# MS_20_Filter_Geetah.net
KiCad netlist of a schematic drawn in EAGLE
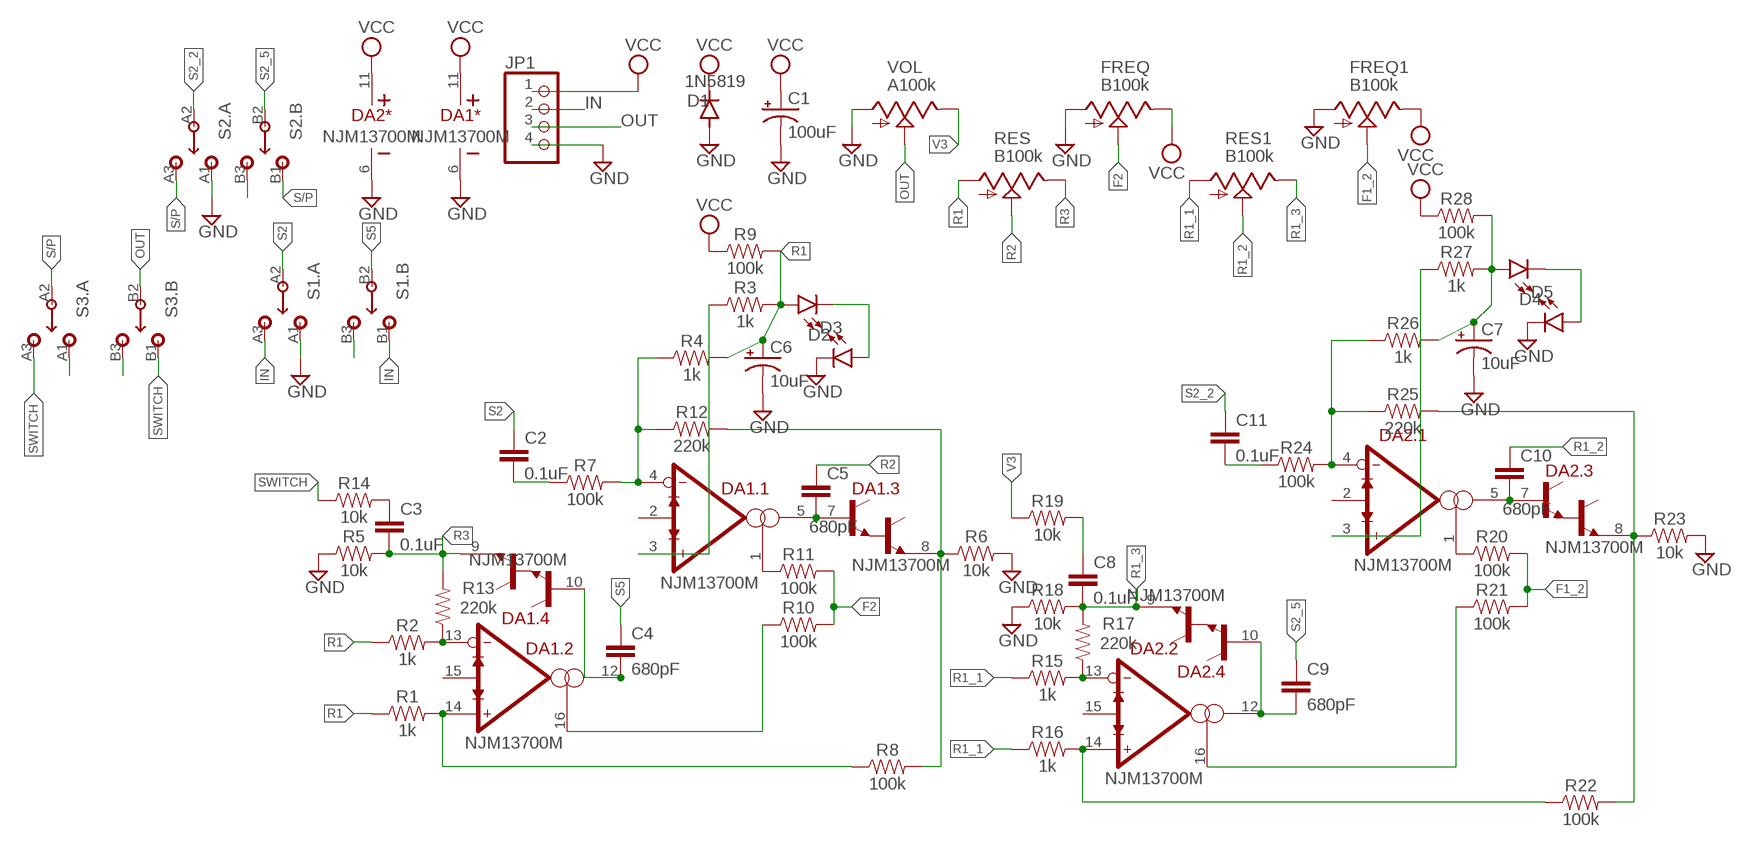
[diagram p0: schematic, sheet 1]

(export (version "E")
  (design (tool "Eeschema 10.0.6"))
  (components
    (comp (ref "C1")
      (value "100uF")
      (footprint "eagle-import:PAN_B_SMD+THRU")
      (libsource (lib "eagle-import") (part "CAP_SMD+THRUPAN_B"))
    )
    (comp (ref "C2")
      (value "0.1uF")
      (footprint "eagle-import:0603")
      (libsource (lib "eagle-import") (part "0.1UF-0603-25V-(+80/-20%)"))
    )
    (comp (ref "C3")
      (value "0.1uF")
      (footprint "eagle-import:0603")
      (libsource (lib "eagle-import") (part "0.1UF-0603-25V-(+80/-20%)"))
    )
    (comp (ref "C4")
      (value "680pF")
      (footprint "eagle-import:0603")
      (libsource (lib "eagle-import") (part "680PF-0603-50V-10%"))
    )
    (comp (ref "C5")
      (value "680pF")
      (footprint "eagle-import:0603")
      (libsource (lib "eagle-import") (part "680PF-0603-50V-10%"))
    )
    (comp (ref "C6")
      (value "10uF")
      (footprint "eagle-import:PAN_B_SMD+THRU")
      (libsource (lib "eagle-import") (part "CAP_SMD+THRUPAN_B"))
    )
    (comp (ref "C7")
      (value "10uF")
      (footprint "eagle-import:PAN_B_SMD+THRU")
      (libsource (lib "eagle-import") (part "CAP_SMD+THRUPAN_B"))
    )
    (comp (ref "C8")
      (value "0.1uF")
      (footprint "eagle-import:0603")
      (libsource (lib "eagle-import") (part "0.1UF-0603-25V-(+80/-20%)"))
    )
    (comp (ref "C9")
      (value "680pF")
      (footprint "eagle-import:0603")
      (libsource (lib "eagle-import") (part "680PF-0603-50V-10%"))
    )
    (comp (ref "C10")
      (value "680pF")
      (footprint "eagle-import:0603")
      (libsource (lib "eagle-import") (part "680PF-0603-50V-10%"))
    )
    (comp (ref "C11")
      (value "0.1uF")
      (footprint "eagle-import:0603")
      (libsource (lib "eagle-import") (part "0.1UF-0603-25V-(+80/-20%)"))
    )
    (comp (ref "D1")
      (value "1N5819")
      (footprint "eagle-import:SOD123")
      (libsource (lib "eagle-import") (part "DIODE-SOD123"))
    )
    (comp (ref "D2")
      (value "LED-FKIT-1206")
      (footprint "eagle-import:FKIT-LED-1206")
      (libsource (lib "eagle-import") (part "LED-FKIT-1206"))
    )
    (comp (ref "D3")
      (value "LED-FKIT-1206")
      (footprint "eagle-import:FKIT-LED-1206")
      (libsource (lib "eagle-import") (part "LED-FKIT-1206"))
    )
    (comp (ref "D4")
      (value "LED-FKIT-1206")
      (footprint "eagle-import:FKIT-LED-1206")
      (libsource (lib "eagle-import") (part "LED-FKIT-1206"))
    )
    (comp (ref "D5")
      (value "LED-FKIT-1206")
      (footprint "eagle-import:FKIT-LED-1206")
      (libsource (lib "eagle-import") (part "LED-FKIT-1206"))
    )
    (comp (ref "DA1")
      (value "NJM13700M")
      (footprint "eagle-import:SO-16")
      (libsource (lib "eagle-import") (part "NJM13700M"))
    )
    (comp (ref "DA2")
      (value "NJM13700M")
      (footprint "eagle-import:SO-16")
      (libsource (lib "eagle-import") (part "NJM13700M"))
    )
    (comp (ref "FREQ")
      (value "B100k")
      (footprint "eagle-import:9MM_SNAP-IN_POT")
      (libsource (lib "eagle-import") (part "9MM_SNAP-IN_POT_"))
    )
    (comp (ref "FREQ1")
      (value "B100k")
      (footprint "eagle-import:9MM_SNAP-IN_POT")
      (libsource (lib "eagle-import") (part "9MM_SNAP-IN_POT_"))
    )
    (comp (ref "JP1")
      (value "PINHD-1X4")
      (footprint "eagle-import:1X04")
      (libsource (lib "eagle-import") (part "PINHD-1X4"))
    )
    (comp (ref "R1")
      (value "1k")
      (footprint "eagle-import:0603")
      (libsource (lib "eagle-import") (part "1KOHM-0603-1/10W-1%"))
    )
    (comp (ref "R2")
      (value "1k")
      (footprint "eagle-import:0603")
      (libsource (lib "eagle-import") (part "1KOHM-0603-1/10W-1%"))
    )
    (comp (ref "R3")
      (value "1k")
      (footprint "eagle-import:0603")
      (libsource (lib "eagle-import") (part "1KOHM-0603-1/10W-1%"))
    )
    (comp (ref "R4")
      (value "1k")
      (footprint "eagle-import:0603")
      (libsource (lib "eagle-import") (part "1KOHM-0603-1/10W-1%"))
    )
    (comp (ref "R5")
      (value "10k")
      (footprint "eagle-import:0603")
      (libsource (lib "eagle-import") (part "10KOHM-0603-1/10W-1%"))
    )
    (comp (ref "R6")
      (value "10k")
      (footprint "eagle-import:0603")
      (libsource (lib "eagle-import") (part "10KOHM-0603-1/10W-1%"))
    )
    (comp (ref "R7")
      (value "100k")
      (footprint "eagle-import:0603")
      (libsource (lib "eagle-import") (part "100KOHM-0603-1/10W-1%"))
    )
    (comp (ref "R8")
      (value "100k")
      (footprint "eagle-import:0603")
      (libsource (lib "eagle-import") (part "100KOHM-0603-1/10W-1%"))
    )
    (comp (ref "R9")
      (value "100k")
      (footprint "eagle-import:0603")
      (libsource (lib "eagle-import") (part "100KOHM-0603-1/10W-1%"))
    )
    (comp (ref "R10")
      (value "100k")
      (footprint "eagle-import:0603")
      (libsource (lib "eagle-import") (part "100KOHM-0603-1/10W-1%"))
    )
    (comp (ref "R11")
      (value "100k")
      (footprint "eagle-import:0603")
      (libsource (lib "eagle-import") (part "100KOHM-0603-1/10W-1%"))
    )
    (comp (ref "R12")
      (value "220k")
      (footprint "eagle-import:0603")
      (libsource (lib "eagle-import") (part "220KOHM-0603-1/10W-1%"))
    )
    (comp (ref "R13")
      (value "220k")
      (footprint "eagle-import:0603")
      (libsource (lib "eagle-import") (part "220KOHM-0603-1/10W-1%"))
    )
    (comp (ref "R14")
      (value "10k")
      (footprint "eagle-import:0603")
      (libsource (lib "eagle-import") (part "10KOHM-0603-1/10W-1%"))
    )
    (comp (ref "R15")
      (value "1k")
      (footprint "eagle-import:0603")
      (libsource (lib "eagle-import") (part "1KOHM-0603-1/10W-1%"))
    )
    (comp (ref "R16")
      (value "1k")
      (footprint "eagle-import:0603")
      (libsource (lib "eagle-import") (part "1KOHM-0603-1/10W-1%"))
    )
    (comp (ref "R17")
      (value "220k")
      (footprint "eagle-import:0603")
      (libsource (lib "eagle-import") (part "220KOHM-0603-1/10W-1%"))
    )
    (comp (ref "R18")
      (value "10k")
      (footprint "eagle-import:0603")
      (libsource (lib "eagle-import") (part "10KOHM-0603-1/10W-1%"))
    )
    (comp (ref "R19")
      (value "10k")
      (footprint "eagle-import:0603")
      (libsource (lib "eagle-import") (part "10KOHM-0603-1/10W-1%"))
    )
    (comp (ref "R20")
      (value "100k")
      (footprint "eagle-import:0603")
      (libsource (lib "eagle-import") (part "100KOHM-0603-1/10W-1%"))
    )
    (comp (ref "R21")
      (value "100k")
      (footprint "eagle-import:0603")
      (libsource (lib "eagle-import") (part "100KOHM-0603-1/10W-1%"))
    )
    (comp (ref "R22")
      (value "100k")
      (footprint "eagle-import:0603")
      (libsource (lib "eagle-import") (part "100KOHM-0603-1/10W-1%"))
    )
    (comp (ref "R23")
      (value "10k")
      (footprint "eagle-import:0603")
      (libsource (lib "eagle-import") (part "10KOHM-0603-1/10W-1%"))
    )
    (comp (ref "R24")
      (value "100k")
      (footprint "eagle-import:0603")
      (libsource (lib "eagle-import") (part "100KOHM-0603-1/10W-1%"))
    )
    (comp (ref "R25")
      (value "220k")
      (footprint "eagle-import:0603")
      (libsource (lib "eagle-import") (part "220KOHM-0603-1/10W-1%"))
    )
    (comp (ref "R26")
      (value "1k")
      (footprint "eagle-import:0603")
      (libsource (lib "eagle-import") (part "1KOHM-0603-1/10W-1%"))
    )
    (comp (ref "R27")
      (value "1k")
      (footprint "eagle-import:0603")
      (libsource (lib "eagle-import") (part "1KOHM-0603-1/10W-1%"))
    )
    (comp (ref "R28")
      (value "100k")
      (footprint "eagle-import:0603")
      (libsource (lib "eagle-import") (part "100KOHM-0603-1/10W-1%"))
    )
    (comp (ref "RES")
      (value "B100k")
      (footprint "eagle-import:9MM_SNAP-IN_POT")
      (libsource (lib "eagle-import") (part "9MM_SNAP-IN_POT_"))
    )
    (comp (ref "RES1")
      (value "B100k")
      (footprint "eagle-import:9MM_SNAP-IN_POT")
      (libsource (lib "eagle-import") (part "9MM_SNAP-IN_POT_"))
    )
    (comp (ref "S1")
      (value "DPDT.LUGS")
      (footprint "eagle-import:DPDT.LUGS")
      (libsource (lib "eagle-import") (part "DPDT.LUGS"))
    )
    (comp (ref "S2")
      (value "DPDT.LUGS")
      (footprint "eagle-import:DPDT.LUGS")
      (libsource (lib "eagle-import") (part "DPDT.LUGS"))
    )
    (comp (ref "S3")
      (value "DPDT.LUGS")
      (footprint "eagle-import:DPDT.LUGS")
      (libsource (lib "eagle-import") (part "DPDT.LUGS"))
    )
    (comp (ref "VOL")
      (value "A100k")
      (footprint "eagle-import:9MM_SNAP-IN_POT")
      (libsource (lib "eagle-import") (part "9MM_SNAP-IN_POT_"))
    )
  )
  (nets
    (net (code "1") (name "F1_2") (class "Default")
      (node (ref "FREQ1") (pin "2") (pinfunction "S_2") (pintype "passive"))
      (node (ref "R20") (pin "2") (pinfunction "2_2") (pintype "passive"))
      (node (ref "R21") (pin "2") (pinfunction "2_2") (pintype "passive"))
    )
    (net (code "2") (name "F2") (class "Default")
      (node (ref "FREQ") (pin "2") (pinfunction "S_2") (pintype "passive"))
      (node (ref "R10") (pin "2") (pinfunction "2_2") (pintype "passive"))
      (node (ref "R11") (pin "2") (pinfunction "2_2") (pintype "passive"))
    )
    (net (code "3") (name "GND") (class "Default")
      (node (ref "C1") (pin "-") (pinfunction "-_-") (pintype "passive"))
      (node (ref "C1") (pin "--") (pinfunction "-_--") (pintype "passive"))
      (node (ref "C6") (pin "-") (pinfunction "-_-") (pintype "passive"))
      (node (ref "C6") (pin "--") (pinfunction "-_--") (pintype "passive"))
      (node (ref "C7") (pin "-") (pinfunction "-_-") (pintype "passive"))
      (node (ref "C7") (pin "--") (pinfunction "-_--") (pintype "passive"))
      (node (ref "D1") (pin "A") (pinfunction "A_A") (pintype "passive"))
      (node (ref "D3") (pin "C") (pinfunction "C_C") (pintype "passive"))
      (node (ref "D5") (pin "C") (pinfunction "C_C") (pintype "passive"))
      (node (ref "DA1") (pin "6") (pinfunction "V-_6") (pintype "power_in"))
      (node (ref "DA2") (pin "6") (pinfunction "V-_6") (pintype "power_in"))
      (node (ref "FREQ") (pin "1") (pinfunction "A_1") (pintype "passive"))
      (node (ref "FREQ1") (pin "1") (pinfunction "A_1") (pintype "passive"))
      (node (ref "JP1") (pin "4") (pinfunction "4_4") (pintype "passive"))
      (node (ref "R18") (pin "1") (pinfunction "1_1") (pintype "passive"))
      (node (ref "R23") (pin "2") (pinfunction "2_2") (pintype "passive"))
      (node (ref "R5") (pin "1") (pinfunction "1_1") (pintype "passive"))
      (node (ref "R6") (pin "2") (pinfunction "2_2") (pintype "passive"))
      (node (ref "S1") (pin "A1") (pinfunction "1_A1") (pintype "passive"))
      (node (ref "S2") (pin "A1") (pinfunction "1_A1") (pintype "passive"))
      (node (ref "VOL") (pin "1") (pinfunction "A_1") (pintype "passive"))
    )
    (net (code "4") (name "IN") (class "Default")
      (node (ref "JP1") (pin "2") (pinfunction "2_2") (pintype "passive"))
      (node (ref "S1") (pin "A3") (pinfunction "3_A3") (pintype "passive"))
      (node (ref "S1") (pin "B1") (pinfunction "1_B1") (pintype "passive"))
    )
    (net (code "5") (name "Net-(C2-Pad2)") (class "Default")
      (node (ref "C2") (pin "2") (pinfunction "2_2") (pintype "passive"))
      (node (ref "R7") (pin "1") (pinfunction "1_1") (pintype "passive"))
    )
    (net (code "6") (name "Net-(C3-Pad1)") (class "Default")
      (node (ref "C3") (pin "1") (pinfunction "1_1") (pintype "passive"))
      (node (ref "R14") (pin "2") (pinfunction "2_2") (pintype "passive"))
    )
    (net (code "7") (name "Net-(C7-+-Pad++)") (class "Default")
      (node (ref "C7") (pin "+") (pinfunction "+_+") (pintype "passive"))
      (node (ref "C7") (pin "++") (pinfunction "+_++") (pintype "passive"))
      (node (ref "D4") (pin "A") (pinfunction "A_A") (pintype "passive"))
      (node (ref "R26") (pin "2") (pinfunction "2_2") (pintype "passive"))
      (node (ref "R27") (pin "2") (pinfunction "2_2") (pintype "passive"))
      (node (ref "R28") (pin "2") (pinfunction "2_2") (pintype "passive"))
    )
    (net (code "8") (name "Net-(C8-Pad1)") (class "Default")
      (node (ref "C8") (pin "1") (pinfunction "1_1") (pintype "passive"))
      (node (ref "R19") (pin "2") (pinfunction "2_2") (pintype "passive"))
    )
    (net (code "9") (name "Net-(C11-Pad2)") (class "Default")
      (node (ref "C11") (pin "2") (pinfunction "2_2") (pintype "passive"))
      (node (ref "R24") (pin "1") (pinfunction "1_1") (pintype "passive"))
    )
    (net (code "10") (name "Net-(D2-PadC)") (class "Default")
      (node (ref "D2") (pin "C") (pinfunction "C_C") (pintype "passive"))
      (node (ref "D3") (pin "A") (pinfunction "A_A") (pintype "passive"))
    )
    (net (code "11") (name "Net-(D4-PadC)") (class "Default")
      (node (ref "D4") (pin "C") (pinfunction "C_C") (pintype "passive"))
      (node (ref "D5") (pin "A") (pinfunction "A_A") (pintype "passive"))
    )
    (net (code "12") (name "Net-(DA1B-AMP_BIAS)") (class "Default")
      (node (ref "DA1") (pin "1") (pinfunction "AMP_BIAS_1") (pintype "input"))
      (node (ref "R11") (pin "1") (pinfunction "1_1") (pintype "passive"))
    )
    (net (code "13") (name "Net-(DA1B-IN+)") (class "Default")
      (node (ref "DA1") (pin "3") (pinfunction "IN+_3") (pintype "input"))
      (node (ref "R3") (pin "1") (pinfunction "1_1") (pintype "passive"))
    )
    (net (code "14") (name "Net-(DA1B-IN-)") (class "Default")
      (node (ref "DA1") (pin "4") (pinfunction "IN-_4") (pintype "input"))
      (node (ref "R12") (pin "1") (pinfunction "1_1") (pintype "passive"))
      (node (ref "R4") (pin "1") (pinfunction "1_1") (pintype "passive"))
      (node (ref "R7") (pin "2") (pinfunction "2_2") (pintype "passive"))
    )
    (net (code "15") (name "Net-(DA1B-OUT)") (class "Default")
      (node (ref "C5") (pin "2") (pinfunction "2_2") (pintype "passive"))
      (node (ref "DA1") (pin "5") (pinfunction "OUT_5") (pintype "output"))
      (node (ref "DA1") (pin "7") (pinfunction "B_7") (pintype "passive"))
    )
    (net (code "16") (name "Net-(DA1C-AMP_BIAS)") (class "Default")
      (node (ref "DA1") (pin "16") (pinfunction "AMP_BIAS_16") (pintype "input"))
      (node (ref "R10") (pin "1") (pinfunction "1_1") (pintype "passive"))
    )
    (net (code "17") (name "Net-(DA1C-IN+)") (class "Default")
      (node (ref "DA1") (pin "14") (pinfunction "IN+_14") (pintype "input"))
      (node (ref "R1") (pin "2") (pinfunction "2_2") (pintype "passive"))
      (node (ref "R8") (pin "1") (pinfunction "1_1") (pintype "passive"))
    )
    (net (code "18") (name "Net-(DA1C-IN-)") (class "Default")
      (node (ref "DA1") (pin "13") (pinfunction "IN-_13") (pintype "input"))
      (node (ref "R13") (pin "1") (pinfunction "1_1") (pintype "passive"))
      (node (ref "R2") (pin "2") (pinfunction "2_2") (pintype "passive"))
    )
    (net (code "19") (name "Net-(DA1C-OUT)") (class "Default")
      (node (ref "C4") (pin "2") (pinfunction "2_2") (pintype "passive"))
      (node (ref "DA1") (pin "10") (pinfunction "B_10") (pintype "passive"))
      (node (ref "DA1") (pin "12") (pinfunction "OUT_12") (pintype "output"))
    )
    (net (code "20") (name "Net-(DA1D-E)") (class "Default")
      (node (ref "DA1") (pin "8") (pinfunction "E_8") (pintype "passive"))
      (node (ref "R12") (pin "2") (pinfunction "2_2") (pintype "passive"))
      (node (ref "R6") (pin "1") (pinfunction "1_1") (pintype "passive"))
      (node (ref "R8") (pin "2") (pinfunction "2_2") (pintype "passive"))
    )
    (net (code "21") (name "Net-(DA2B-AMP_BIAS)") (class "Default")
      (node (ref "DA2") (pin "1") (pinfunction "AMP_BIAS_1") (pintype "input"))
      (node (ref "R20") (pin "1") (pinfunction "1_1") (pintype "passive"))
    )
    (net (code "22") (name "Net-(DA2B-IN+)") (class "Default")
      (node (ref "DA2") (pin "3") (pinfunction "IN+_3") (pintype "input"))
      (node (ref "R27") (pin "1") (pinfunction "1_1") (pintype "passive"))
    )
    (net (code "23") (name "Net-(DA2B-IN-)") (class "Default")
      (node (ref "DA2") (pin "4") (pinfunction "IN-_4") (pintype "input"))
      (node (ref "R24") (pin "2") (pinfunction "2_2") (pintype "passive"))
      (node (ref "R25") (pin "1") (pinfunction "1_1") (pintype "passive"))
      (node (ref "R26") (pin "1") (pinfunction "1_1") (pintype "passive"))
    )
    (net (code "24") (name "Net-(DA2B-OUT)") (class "Default")
      (node (ref "C10") (pin "2") (pinfunction "2_2") (pintype "passive"))
      (node (ref "DA2") (pin "5") (pinfunction "OUT_5") (pintype "output"))
      (node (ref "DA2") (pin "7") (pinfunction "B_7") (pintype "passive"))
    )
    (net (code "25") (name "Net-(DA2C-AMP_BIAS)") (class "Default")
      (node (ref "DA2") (pin "16") (pinfunction "AMP_BIAS_16") (pintype "input"))
      (node (ref "R21") (pin "1") (pinfunction "1_1") (pintype "passive"))
    )
    (net (code "26") (name "Net-(DA2C-IN+)") (class "Default")
      (node (ref "DA2") (pin "14") (pinfunction "IN+_14") (pintype "input"))
      (node (ref "R16") (pin "2") (pinfunction "2_2") (pintype "passive"))
      (node (ref "R22") (pin "1") (pinfunction "1_1") (pintype "passive"))
    )
    (net (code "27") (name "Net-(DA2C-IN-)") (class "Default")
      (node (ref "DA2") (pin "13") (pinfunction "IN-_13") (pintype "input"))
      (node (ref "R15") (pin "2") (pinfunction "2_2") (pintype "passive"))
      (node (ref "R17") (pin "1") (pinfunction "1_1") (pintype "passive"))
    )
    (net (code "28") (name "Net-(DA2C-OUT)") (class "Default")
      (node (ref "C9") (pin "2") (pinfunction "2_2") (pintype "passive"))
      (node (ref "DA2") (pin "10") (pinfunction "B_10") (pintype "passive"))
      (node (ref "DA2") (pin "12") (pinfunction "OUT_12") (pintype "output"))
    )
    (net (code "29") (name "Net-(DA2D-E)") (class "Default")
      (node (ref "DA2") (pin "8") (pinfunction "E_8") (pintype "passive"))
      (node (ref "R22") (pin "2") (pinfunction "2_2") (pintype "passive"))
      (node (ref "R23") (pin "1") (pinfunction "1_1") (pintype "passive"))
      (node (ref "R25") (pin "2") (pinfunction "2_2") (pintype "passive"))
    )
    (net (code "30") (name "OUT") (class "Default")
      (node (ref "JP1") (pin "3") (pinfunction "3_3") (pintype "passive"))
      (node (ref "S3") (pin "B2") (pinfunction "2_B2") (pintype "passive"))
      (node (ref "VOL") (pin "2") (pinfunction "S_2") (pintype "passive"))
    )
    (net (code "31") (name "R1") (class "Default")
      (node (ref "C6") (pin "+") (pinfunction "+_+") (pintype "passive"))
      (node (ref "C6") (pin "++") (pinfunction "+_++") (pintype "passive"))
      (node (ref "D2") (pin "A") (pinfunction "A_A") (pintype "passive"))
      (node (ref "R1") (pin "1") (pinfunction "1_1") (pintype "passive"))
      (node (ref "R2") (pin "1") (pinfunction "1_1") (pintype "passive"))
      (node (ref "R3") (pin "2") (pinfunction "2_2") (pintype "passive"))
      (node (ref "R4") (pin "2") (pinfunction "2_2") (pintype "passive"))
      (node (ref "R9") (pin "2") (pinfunction "2_2") (pintype "passive"))
      (node (ref "RES") (pin "1") (pinfunction "A_1") (pintype "passive"))
    )
    (net (code "32") (name "R1_1") (class "Default")
      (node (ref "R15") (pin "1") (pinfunction "1_1") (pintype "passive"))
      (node (ref "R16") (pin "1") (pinfunction "1_1") (pintype "passive"))
      (node (ref "RES1") (pin "1") (pinfunction "A_1") (pintype "passive"))
    )
    (net (code "33") (name "R1_2") (class "Default")
      (node (ref "C10") (pin "1") (pinfunction "1_1") (pintype "passive"))
      (node (ref "RES1") (pin "2") (pinfunction "S_2") (pintype "passive"))
    )
    (net (code "34") (name "R1_3") (class "Default")
      (node (ref "C8") (pin "2") (pinfunction "2_2") (pintype "passive"))
      (node (ref "DA2") (pin "9") (pinfunction "E_9") (pintype "passive"))
      (node (ref "R17") (pin "2") (pinfunction "2_2") (pintype "passive"))
      (node (ref "R18") (pin "2") (pinfunction "2_2") (pintype "passive"))
      (node (ref "RES1") (pin "3") (pinfunction "E_3") (pintype "passive"))
    )
    (net (code "35") (name "R2") (class "Default")
      (node (ref "C5") (pin "1") (pinfunction "1_1") (pintype "passive"))
      (node (ref "RES") (pin "2") (pinfunction "S_2") (pintype "passive"))
    )
    (net (code "36") (name "R3") (class "Default")
      (node (ref "C3") (pin "2") (pinfunction "2_2") (pintype "passive"))
      (node (ref "DA1") (pin "9") (pinfunction "E_9") (pintype "passive"))
      (node (ref "R13") (pin "2") (pinfunction "2_2") (pintype "passive"))
      (node (ref "R5") (pin "2") (pinfunction "2_2") (pintype "passive"))
      (node (ref "RES") (pin "3") (pinfunction "E_3") (pintype "passive"))
    )
    (net (code "37") (name "S2") (class "Default")
      (node (ref "C2") (pin "1") (pinfunction "1_1") (pintype "passive"))
      (node (ref "S1") (pin "A2") (pinfunction "2_A2") (pintype "passive"))
    )
    (net (code "38") (name "S2_2") (class "Default")
      (node (ref "C11") (pin "1") (pinfunction "1_1") (pintype "passive"))
      (node (ref "S2") (pin "A2") (pinfunction "2_A2") (pintype "passive"))
    )
    (net (code "39") (name "S2_5") (class "Default")
      (node (ref "C9") (pin "1") (pinfunction "1_1") (pintype "passive"))
      (node (ref "S2") (pin "B2") (pinfunction "2_B2") (pintype "passive"))
    )
    (net (code "40") (name "S5") (class "Default")
      (node (ref "C4") (pin "1") (pinfunction "1_1") (pintype "passive"))
      (node (ref "S1") (pin "B2") (pinfunction "2_B2") (pintype "passive"))
    )
    (net (code "41") (name "SWITCH") (class "Default")
      (node (ref "R14") (pin "1") (pinfunction "1_1") (pintype "passive"))
      (node (ref "S3") (pin "A3") (pinfunction "3_A3") (pintype "passive"))
      (node (ref "S3") (pin "B1") (pinfunction "1_B1") (pintype "passive"))
    )
    (net (code "42") (name "S{slash}P") (class "Default")
      (node (ref "S2") (pin "A3") (pinfunction "3_A3") (pintype "passive"))
      (node (ref "S2") (pin "B1") (pinfunction "1_B1") (pintype "passive"))
      (node (ref "S3") (pin "A2") (pinfunction "2_A2") (pintype "passive"))
    )
    (net (code "43") (name "V3") (class "Default")
      (node (ref "R19") (pin "1") (pinfunction "1_1") (pintype "passive"))
      (node (ref "VOL") (pin "3") (pinfunction "E_3") (pintype "passive"))
    )
    (net (code "44") (name "VCC") (class "Default")
      (node (ref "C1") (pin "+") (pinfunction "+_+") (pintype "passive"))
      (node (ref "C1") (pin "++") (pinfunction "+_++") (pintype "passive"))
      (node (ref "D1") (pin "C") (pinfunction "C_C") (pintype "passive"))
      (node (ref "DA1") (pin "11") (pinfunction "V+_11") (pintype "power_in"))
      (node (ref "DA2") (pin "11") (pinfunction "V+_11") (pintype "power_in"))
      (node (ref "FREQ") (pin "3") (pinfunction "E_3") (pintype "passive"))
      (node (ref "FREQ1") (pin "3") (pinfunction "E_3") (pintype "passive"))
      (node (ref "JP1") (pin "1") (pinfunction "1_1") (pintype "passive"))
      (node (ref "R28") (pin "1") (pinfunction "1_1") (pintype "passive"))
      (node (ref "R9") (pin "1") (pinfunction "1_1") (pintype "passive"))
    )
    (net (code "45") (name "unconnected-(DA1B-DIODE_BIAS-Pad2)") (class "Default")
      (node (ref "DA1") (pin "2") (pinfunction "DIODE_BIAS_2") (pintype "input"))
    )
    (net (code "46") (name "unconnected-(DA1C-DIODE_BIAS-Pad15)") (class "Default")
      (node (ref "DA1") (pin "15") (pinfunction "DIODE_BIAS_15") (pintype "input"))
    )
    (net (code "47") (name "unconnected-(DA2B-DIODE_BIAS-Pad2)") (class "Default")
      (node (ref "DA2") (pin "2") (pinfunction "DIODE_BIAS_2") (pintype "input"))
    )
    (net (code "48") (name "unconnected-(DA2C-DIODE_BIAS-Pad15)") (class "Default")
      (node (ref "DA2") (pin "15") (pinfunction "DIODE_BIAS_15") (pintype "input"))
    )
    (net (code "49") (name "unconnected-(S1B-3-PadB3)") (class "Default")
      (node (ref "S1") (pin "B3") (pinfunction "3_B3") (pintype "passive"))
    )
    (net (code "50") (name "unconnected-(S2B-3-PadB3)") (class "Default")
      (node (ref "S2") (pin "B3") (pinfunction "3_B3") (pintype "passive"))
    )
    (net (code "51") (name "unconnected-(S3A-1-PadA1)") (class "Default")
      (node (ref "S3") (pin "A1") (pinfunction "1_A1") (pintype "passive"))
    )
    (net (code "52") (name "unconnected-(S3B-3-PadB3)") (class "Default")
      (node (ref "S3") (pin "B3") (pinfunction "3_B3") (pintype "passive"))
    )
  )
)
